# 08_Peripherals.net
KiCad netlist of a schematic drawn in Altium Designer
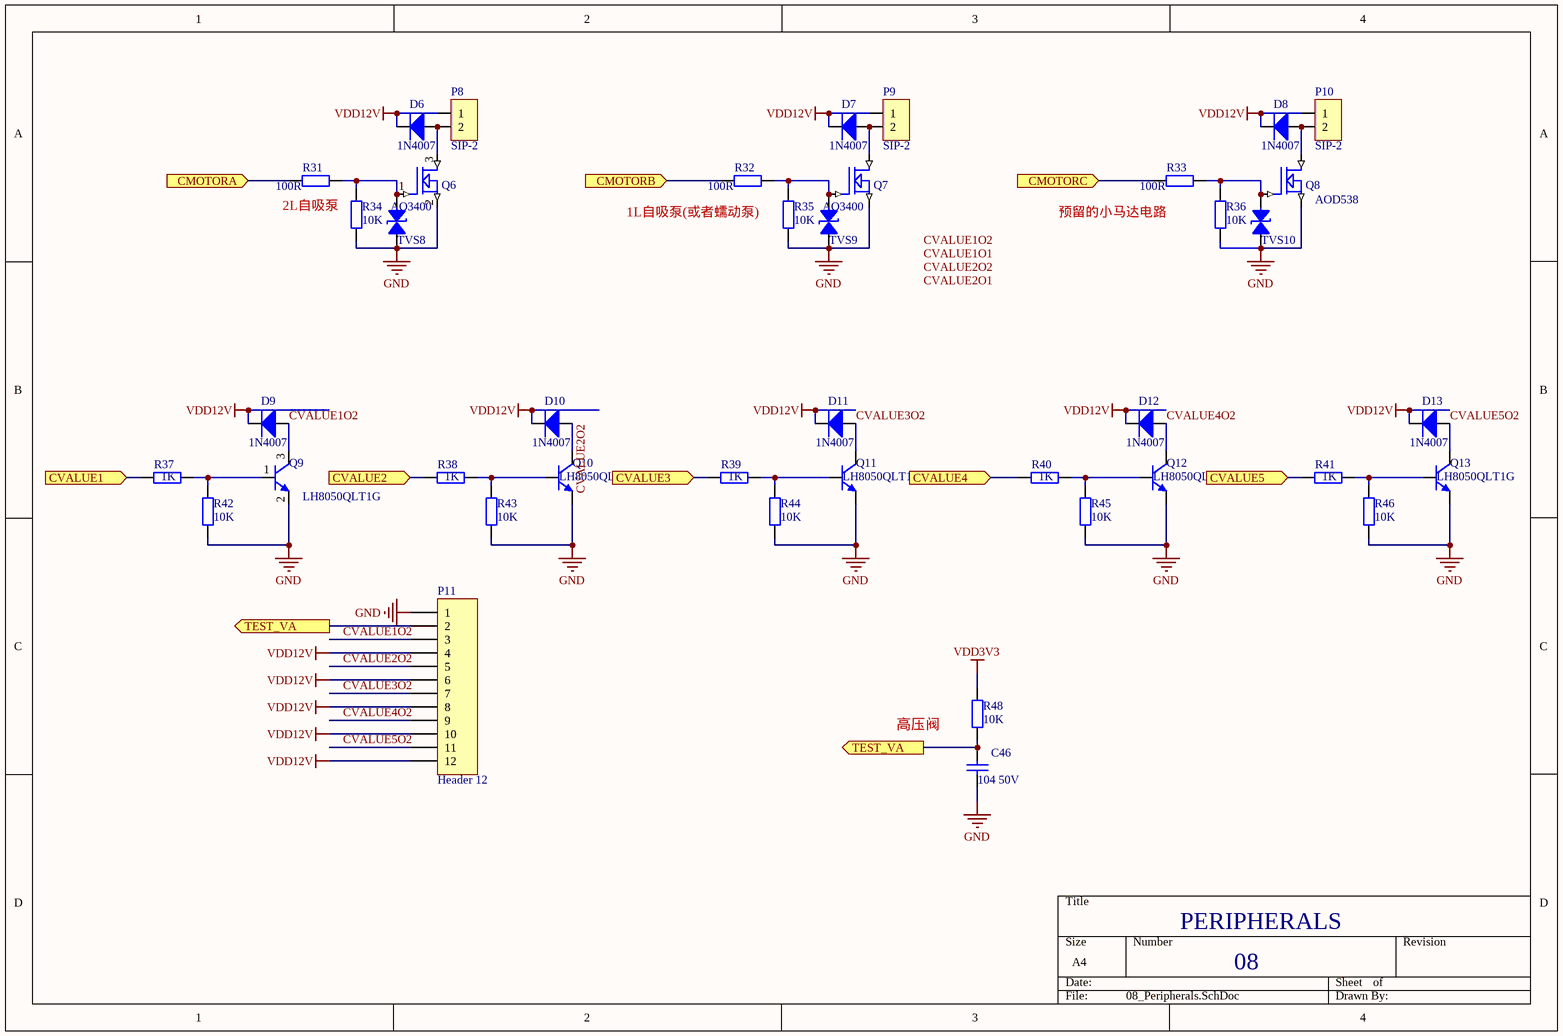
[diagram p0: 08_Peripherals.SchDoc]

(export (version "E")
  (design (tool "Eeschema 10.0.6"))
  (components
    (comp (ref "C46")
      (value "104 50V")
      (footprint "SMD-0603C")
      (description "贴片电容 10%")
      (libsource (lib "XiaoyI") (part "CAP4"))
    )
    (comp (ref "D6")
      (value "1N4007")
      (footprint "DO-214-AC")
      (description "贴片二极管")
      (libsource (lib "XiaoyI") (part "DIODE2"))
    )
    (comp (ref "D7")
      (value "1N4007")
      (footprint "DO-214-AC")
      (description "贴片二极管")
      (libsource (lib "XiaoyI") (part "DIODE2"))
    )
    (comp (ref "D8")
      (value "1N4007")
      (footprint "DO-214-AC")
      (description "贴片二极管")
      (libsource (lib "XiaoyI") (part "DIODE2"))
    )
    (comp (ref "D9")
      (value "1N4007")
      (footprint "DO-214-AC")
      (description "贴片二极管")
      (libsource (lib "XiaoyI") (part "DIODE2"))
    )
    (comp (ref "D10")
      (value "1N4007")
      (footprint "DO-214-AC")
      (description "贴片二极管")
      (libsource (lib "XiaoyI") (part "DIODE2"))
    )
    (comp (ref "D11")
      (value "1N4007")
      (footprint "DO-214-AC")
      (description "贴片二极管")
      (libsource (lib "XiaoyI") (part "DIODE2"))
    )
    (comp (ref "D12")
      (value "1N4007")
      (footprint "DO-214-AC")
      (description "贴片二极管")
      (libsource (lib "XiaoyI") (part "DIODE2"))
    )
    (comp (ref "D13")
      (value "1N4007")
      (footprint "DO-214-AC")
      (description "贴片二极管")
      (libsource (lib "XiaoyI") (part "DIODE2"))
    )
    (comp (ref "P8")
      (value "SIP-2")
      (footprint "SIP-2A")
      (description "XH2.54 2P 立贴")
      (libsource (lib "XiaoyI") (part "SIP-2"))
    )
    (comp (ref "P9")
      (value "SIP-2")
      (footprint "SIP-2A")
      (description "XH2.54 2P 立贴")
      (libsource (lib "XiaoyI") (part "SIP-2"))
    )
    (comp (ref "P10")
      (value "SIP-2")
      (footprint "VH-AW-3.96*2P")
      (description "XH2.54 2P 立贴")
      (libsource (lib "XiaoyI") (part "SIP-2"))
    )
    (comp (ref "P11")
      (value "Header 12")
      (footprint "12X2.54MMZ")
      (description "Header, 12-Pin")
      (fields (field (name "PUBLISHER") "Altium Limited"))
      (libsource (lib "Miscellaneous Connectors") (part "Header 12"))
    )
    (comp (ref "Q6")
      (value "AO3400")
      (footprint "SOT-23")
      (description "MOSFET N")
      (libsource (lib "XiaoyI") (part "MOSFET N"))
    )
    (comp (ref "Q7")
      (value "AO3400")
      (footprint "SOT-23")
      (description "MOSFET N")
      (libsource (lib "") (part "MOSFET N_1"))
    )
    (comp (ref "Q8")
      (value "AOD538")
      (footprint "TO252")
      (description "MOSFET N")
      (libsource (lib "") (part "MOSFET N_1"))
    )
    (comp (ref "Q9")
      (value "LH8050QLT1G")
      (footprint "SOT-23")
      (description "三极管")
      (libsource (lib "") (part "NPN-1_1"))
    )
    (comp (ref "Q10")
      (value "LH8050QLT1G")
      (footprint "SOT-23")
      (description "三极管")
      (libsource (lib "XiaoyI") (part "NPN-1"))
    )
    (comp (ref "Q11")
      (value "LH8050QLT1G")
      (footprint "SOT-23")
      (description "三极管")
      (libsource (lib "XiaoyI") (part "NPN-1"))
    )
    (comp (ref "Q12")
      (value "LH8050QLT1G")
      (footprint "SOT-23")
      (description "三极管")
      (libsource (lib "XiaoyI") (part "NPN-1"))
    )
    (comp (ref "Q13")
      (value "LH8050QLT1G")
      (footprint "SOT-23")
      (description "三极管")
      (libsource (lib "XiaoyI") (part "NPN-1"))
    )
    (comp (ref "R31")
      (value "100R")
      (footprint "SMD-0603")
      (description "贴片电阻 5%")
      (libsource (lib "") (part "RES-SOP_1"))
    )
    (comp (ref "R32")
      (value "100R")
      (footprint "SMD-0603")
      (description "贴片电阻 5%")
      (libsource (lib "") (part "RES-SOP_1"))
    )
    (comp (ref "R33")
      (value "100R")
      (footprint "SMD-0603")
      (description "贴片电阻 5%")
      (libsource (lib "") (part "RES-SOP_1"))
    )
    (comp (ref "R34")
      (value "10K")
      (footprint "SMD-0603")
      (description "贴片电阻 5%")
      (libsource (lib "") (part "RES-SOP_2"))
    )
    (comp (ref "R35")
      (value "10K")
      (footprint "SMD-0603")
      (description "贴片电阻 5%")
      (libsource (lib "") (part "RES-SOP_2"))
    )
    (comp (ref "R36")
      (value "10K")
      (footprint "SMD-0603")
      (description "贴片电阻 5%")
      (libsource (lib "") (part "RES-SOP_2"))
    )
    (comp (ref "R37")
      (value "1K")
      (footprint "SMD-0603")
      (description "贴片电阻 5%")
      (libsource (lib "") (part "RES-SOP_1"))
    )
    (comp (ref "R38")
      (value "1K")
      (footprint "SMD-0603")
      (description "贴片电阻 5%")
      (libsource (lib "") (part "RES-SOP_1"))
    )
    (comp (ref "R39")
      (value "1K")
      (footprint "SMD-0603")
      (description "贴片电阻 5%")
      (libsource (lib "") (part "RES-SOP_1"))
    )
    (comp (ref "R40")
      (value "1K")
      (footprint "SMD-0603")
      (description "贴片电阻 5%")
      (libsource (lib "") (part "RES-SOP_1"))
    )
    (comp (ref "R41")
      (value "1K")
      (footprint "SMD-0603")
      (description "贴片电阻 5%")
      (libsource (lib "") (part "RES-SOP_1"))
    )
    (comp (ref "R42")
      (value "10K")
      (footprint "SMD-0603")
      (description "贴片电阻 5%")
      (libsource (lib "") (part "RES-SOP_2"))
    )
    (comp (ref "R43")
      (value "10K")
      (footprint "SMD-0603")
      (description "贴片电阻 5%")
      (libsource (lib "") (part "RES-SOP_2"))
    )
    (comp (ref "R44")
      (value "10K")
      (footprint "SMD-0603")
      (description "贴片电阻 5%")
      (libsource (lib "") (part "RES-SOP_2"))
    )
    (comp (ref "R45")
      (value "10K")
      (footprint "SMD-0603")
      (description "贴片电阻 5%")
      (libsource (lib "") (part "RES-SOP_2"))
    )
    (comp (ref "R46")
      (value "10K")
      (footprint "SMD-0603")
      (description "贴片电阻 5%")
      (libsource (lib "") (part "RES-SOP_2"))
    )
    (comp (ref "R48")
      (value "10K")
      (footprint "SMD-0603")
      (description "贴片电阻 5%")
      (libsource (lib "XiaoyI") (part "RES-SOP"))
    )
    (comp (ref "TVS8")
      (value "ESD5Z5.0CT1G")
      (footprint "SOD-523")
      (description "TVS")
      (libsource (lib "XiaoyI") (part "TVS-1"))
    )
    (comp (ref "TVS9")
      (value "ESD5Z5.0CT1G")
      (footprint "SOD-523")
      (description "TVS")
      (libsource (lib "XiaoyI") (part "TVS-1"))
    )
    (comp (ref "TVS10")
      (value "ESD5Z5.0CT1G")
      (footprint "SOD-523")
      (description "TVS")
      (libsource (lib "XiaoyI") (part "TVS-1"))
    )
  )
  (nets
    (net (code "1") (name "/CMOTORA") (class "Default")
      (node (ref "R31") (pin "2") (pinfunction "2_2") (pintype "passive"))
    )
    (net (code "2") (name "/CMOTORB") (class "Default")
      (node (ref "R32") (pin "2") (pinfunction "2_2") (pintype "passive"))
    )
    (net (code "3") (name "/CMOTORC") (class "Default")
      (node (ref "R33") (pin "2") (pinfunction "2_2") (pintype "passive"))
    )
    (net (code "4") (name "/CVALUE1") (class "Default")
      (node (ref "R37") (pin "2") (pinfunction "2_2") (pintype "passive"))
    )
    (net (code "6") (name "/CVALUE1O2") (class "Default")
      (node (ref "D9") (pin "1") (pinfunction "A_1") (pintype "passive"))
      (node (ref "P11") (pin "3") (pinfunction "3_3") (pintype "passive"))
      (node (ref "Q9") (pin "3") (pinfunction "C_3") (pintype "passive"))
    )
    (net (code "7") (name "/CVALUE2") (class "Default")
      (node (ref "R38") (pin "2") (pinfunction "2_2") (pintype "passive"))
    )
    (net (code "9") (name "/CVALUE2O2") (class "Default")
      (node (ref "D10") (pin "1") (pinfunction "A_1") (pintype "passive"))
      (node (ref "P11") (pin "5") (pinfunction "5_5") (pintype "passive"))
      (node (ref "Q10") (pin "3") (pinfunction "C_3") (pintype "passive"))
    )
    (net (code "10") (name "/CVALUE3") (class "Default")
      (node (ref "R39") (pin "2") (pinfunction "2_2") (pintype "passive"))
    )
    (net (code "11") (name "/CVALUE3O2") (class "Default")
      (node (ref "D11") (pin "1") (pinfunction "A_1") (pintype "passive"))
      (node (ref "P11") (pin "7") (pinfunction "7_7") (pintype "passive"))
      (node (ref "Q11") (pin "3") (pinfunction "C_3") (pintype "passive"))
    )
    (net (code "12") (name "/CVALUE4") (class "Default")
      (node (ref "R40") (pin "2") (pinfunction "2_2") (pintype "passive"))
    )
    (net (code "13") (name "/CVALUE4O2") (class "Default")
      (node (ref "D12") (pin "1") (pinfunction "A_1") (pintype "passive"))
      (node (ref "P11") (pin "9") (pinfunction "9_9") (pintype "passive"))
      (node (ref "Q12") (pin "3") (pinfunction "C_3") (pintype "passive"))
    )
    (net (code "14") (name "/CVALUE5") (class "Default")
      (node (ref "R41") (pin "2") (pinfunction "2_2") (pintype "passive"))
    )
    (net (code "15") (name "/CVALUE5O2") (class "Default")
      (node (ref "D13") (pin "1") (pinfunction "A_1") (pintype "passive"))
      (node (ref "P11") (pin "11") (pinfunction "11_11") (pintype "passive"))
      (node (ref "Q13") (pin "3") (pinfunction "C_3") (pintype "passive"))
    )
    (net (code "16") (name "/TEST_VA") (class "Default")
      (node (ref "C46") (pin "2") (pinfunction "2_2") (pintype "passive"))
      (node (ref "P11") (pin "2") (pinfunction "2_2") (pintype "passive"))
      (node (ref "R48") (pin "1") (pinfunction "1_1") (pintype "passive"))
    )
    (net (code "17") (name "GND") (class "Default")
      (node (ref "C46") (pin "1") (pinfunction "1_1") (pintype "passive"))
      (node (ref "P11") (pin "1") (pinfunction "1_1") (pintype "passive"))
      (node (ref "Q10") (pin "2") (pinfunction "E_2") (pintype "passive"))
      (node (ref "Q11") (pin "2") (pinfunction "E_2") (pintype "passive"))
      (node (ref "Q12") (pin "2") (pinfunction "E_2") (pintype "passive"))
      (node (ref "Q13") (pin "2") (pinfunction "E_2") (pintype "passive"))
      (node (ref "Q6") (pin "2") (pinfunction "S_2") (pintype "output"))
      (node (ref "Q7") (pin "2") (pinfunction "S_2") (pintype "output"))
      (node (ref "Q8") (pin "2") (pinfunction "S_2") (pintype "output"))
      (node (ref "Q9") (pin "2") (pinfunction "E_2") (pintype "passive"))
      (node (ref "R34") (pin "2") (pinfunction "2_2") (pintype "passive"))
      (node (ref "R35") (pin "2") (pinfunction "2_2") (pintype "passive"))
      (node (ref "R36") (pin "2") (pinfunction "2_2") (pintype "passive"))
      (node (ref "R42") (pin "2") (pinfunction "2_2") (pintype "passive"))
      (node (ref "R43") (pin "2") (pinfunction "2_2") (pintype "passive"))
      (node (ref "R44") (pin "2") (pinfunction "2_2") (pintype "passive"))
      (node (ref "R45") (pin "2") (pinfunction "2_2") (pintype "passive"))
      (node (ref "R46") (pin "2") (pinfunction "2_2") (pintype "passive"))
      (node (ref "TVS10") (pin "1") (pinfunction "A_1") (pintype "passive"))
      (node (ref "TVS8") (pin "1") (pinfunction "A_1") (pintype "passive"))
      (node (ref "TVS9") (pin "1") (pinfunction "A_1") (pintype "passive"))
    )
    (net (code "18") (name "Net-(D6-A)") (class "Default")
      (node (ref "D6") (pin "1") (pinfunction "A_1") (pintype "passive"))
      (node (ref "P8") (pin "2") (pinfunction "2_2") (pintype "passive"))
      (node (ref "Q6") (pin "3") (pinfunction "D_3") (pintype "input"))
    )
    (net (code "19") (name "Net-(D7-A)") (class "Default")
      (node (ref "D7") (pin "1") (pinfunction "A_1") (pintype "passive"))
      (node (ref "P9") (pin "2") (pinfunction "2_2") (pintype "passive"))
      (node (ref "Q7") (pin "3") (pinfunction "D_3") (pintype "input"))
    )
    (net (code "20") (name "Net-(D8-A)") (class "Default")
      (node (ref "D8") (pin "1") (pinfunction "A_1") (pintype "passive"))
      (node (ref "P10") (pin "2") (pinfunction "2_2") (pintype "passive"))
      (node (ref "Q8") (pin "3") (pinfunction "D_3") (pintype "input"))
    )
    (net (code "21") (name "Net-(Q6-G)") (class "Default")
      (node (ref "Q6") (pin "1") (pinfunction "G_1") (pintype "input"))
      (node (ref "R31") (pin "1") (pinfunction "1_1") (pintype "passive"))
      (node (ref "R34") (pin "1") (pinfunction "1_1") (pintype "passive"))
      (node (ref "TVS8") (pin "2") (pinfunction "B_2") (pintype "passive"))
    )
    (net (code "22") (name "Net-(Q7-G)") (class "Default")
      (node (ref "Q7") (pin "1") (pinfunction "G_1") (pintype "input"))
      (node (ref "R32") (pin "1") (pinfunction "1_1") (pintype "passive"))
      (node (ref "R35") (pin "1") (pinfunction "1_1") (pintype "passive"))
      (node (ref "TVS9") (pin "2") (pinfunction "B_2") (pintype "passive"))
    )
    (net (code "23") (name "Net-(Q8-G)") (class "Default")
      (node (ref "Q8") (pin "1") (pinfunction "G_1") (pintype "input"))
      (node (ref "R33") (pin "1") (pinfunction "1_1") (pintype "passive"))
      (node (ref "R36") (pin "1") (pinfunction "1_1") (pintype "passive"))
      (node (ref "TVS10") (pin "2") (pinfunction "B_2") (pintype "passive"))
    )
    (net (code "24") (name "Net-(Q9-B)") (class "Default")
      (node (ref "Q9") (pin "1") (pinfunction "B_1") (pintype "passive"))
      (node (ref "R37") (pin "1") (pinfunction "1_1") (pintype "passive"))
      (node (ref "R42") (pin "1") (pinfunction "1_1") (pintype "passive"))
    )
    (net (code "25") (name "Net-(Q10-B)") (class "Default")
      (node (ref "Q10") (pin "1") (pinfunction "B_1") (pintype "passive"))
      (node (ref "R38") (pin "1") (pinfunction "1_1") (pintype "passive"))
      (node (ref "R43") (pin "1") (pinfunction "1_1") (pintype "passive"))
    )
    (net (code "26") (name "Net-(Q11-B)") (class "Default")
      (node (ref "Q11") (pin "1") (pinfunction "B_1") (pintype "passive"))
      (node (ref "R39") (pin "1") (pinfunction "1_1") (pintype "passive"))
      (node (ref "R44") (pin "1") (pinfunction "1_1") (pintype "passive"))
    )
    (net (code "27") (name "Net-(Q12-B)") (class "Default")
      (node (ref "Q12") (pin "1") (pinfunction "B_1") (pintype "passive"))
      (node (ref "R40") (pin "1") (pinfunction "1_1") (pintype "passive"))
      (node (ref "R45") (pin "1") (pinfunction "1_1") (pintype "passive"))
    )
    (net (code "28") (name "Net-(Q13-B)") (class "Default")
      (node (ref "Q13") (pin "1") (pinfunction "B_1") (pintype "passive"))
      (node (ref "R41") (pin "1") (pinfunction "1_1") (pintype "passive"))
      (node (ref "R46") (pin "1") (pinfunction "1_1") (pintype "passive"))
    )
    (net (code "29") (name "VDD3V3") (class "Default")
      (node (ref "R48") (pin "2") (pinfunction "2_2") (pintype "passive"))
    )
    (net (code "30") (name "VDD12V") (class "Default")
      (node (ref "D10") (pin "2") (pinfunction "K_2") (pintype "passive"))
      (node (ref "D11") (pin "2") (pinfunction "K_2") (pintype "passive"))
      (node (ref "D12") (pin "2") (pinfunction "K_2") (pintype "passive"))
      (node (ref "D13") (pin "2") (pinfunction "K_2") (pintype "passive"))
      (node (ref "D6") (pin "2") (pinfunction "K_2") (pintype "passive"))
      (node (ref "D7") (pin "2") (pinfunction "K_2") (pintype "passive"))
      (node (ref "D8") (pin "2") (pinfunction "K_2") (pintype "passive"))
      (node (ref "D9") (pin "2") (pinfunction "K_2") (pintype "passive"))
      (node (ref "P10") (pin "1") (pinfunction "1_1") (pintype "passive"))
      (node (ref "P11") (pin "10") (pinfunction "10_10") (pintype "passive"))
      (node (ref "P11") (pin "12") (pinfunction "12_12") (pintype "passive"))
      (node (ref "P11") (pin "4") (pinfunction "4_4") (pintype "passive"))
      (node (ref "P11") (pin "6") (pinfunction "6_6") (pintype "passive"))
      (node (ref "P11") (pin "8") (pinfunction "8_8") (pintype "passive"))
      (node (ref "P8") (pin "1") (pinfunction "1_1") (pintype "passive"))
      (node (ref "P9") (pin "1") (pinfunction "1_1") (pintype "passive"))
    )
  )
)
